# 8_steps_sequencer.net
KiCad netlist of a schematic drawn in EAGLE
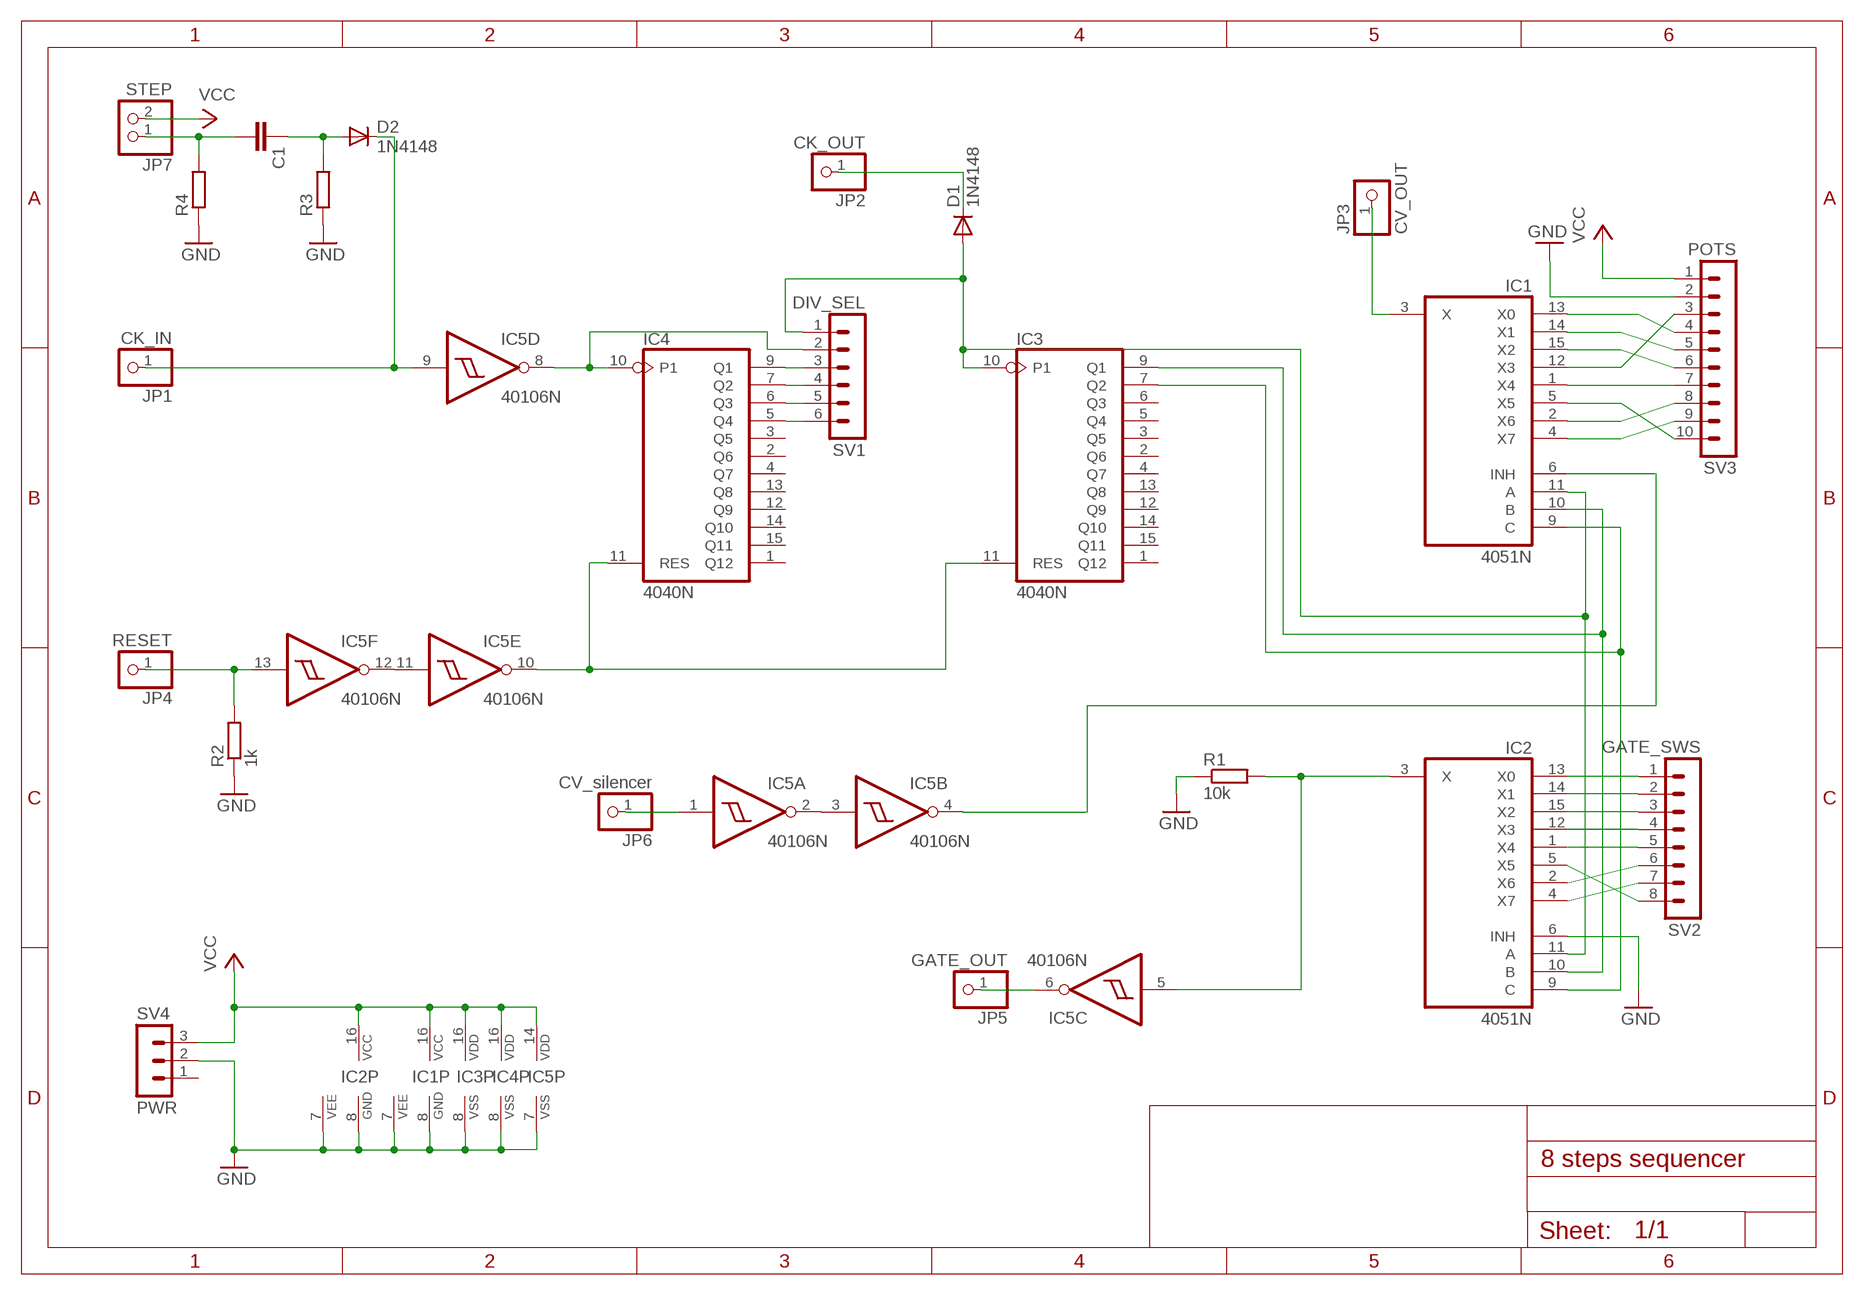
[diagram p0: schematic, sheet 1]

(export (version "E")
  (design (tool "Eeschema 10.0.6"))
  (components
    (comp (ref "C1")
      (value "C-EU025-030X050")
      (footprint "eagle-import:C025-030X050")
      (libsource (lib "eagle-import") (part "C-EU025-030X050"))
    )
    (comp (ref "D1")
      (value "1N4148")
      (footprint "eagle-import:D-2.5")
      (libsource (lib "eagle-import") (part "DIODE-D-2.5"))
    )
    (comp (ref "D2")
      (value "1N4148")
      (footprint "eagle-import:D-2.5")
      (libsource (lib "eagle-import") (part "DIODE-D-2.5"))
    )
    (comp (ref "IC1")
      (value "4051N")
      (footprint "eagle-import:DIL16")
      (libsource (lib "eagle-import") (part "4051N"))
    )
    (comp (ref "IC2")
      (value "4051N")
      (footprint "eagle-import:DIL16")
      (libsource (lib "eagle-import") (part "4051N"))
    )
    (comp (ref "IC3")
      (value "4040N")
      (footprint "eagle-import:DIL16")
      (libsource (lib "eagle-import") (part "4040N"))
    )
    (comp (ref "IC4")
      (value "4040N")
      (footprint "eagle-import:DIL16")
      (libsource (lib "eagle-import") (part "4040N"))
    )
    (comp (ref "IC5")
      (value "40106N")
      (footprint "eagle-import:DIL14")
      (libsource (lib "eagle-import") (part "40106N"))
    )
    (comp (ref "JP1")
      (value "CK_IN")
      (footprint "eagle-import:1X01")
      (libsource (lib "eagle-import") (part "PINHD-1X1"))
    )
    (comp (ref "JP2")
      (value "CK_OUT")
      (footprint "eagle-import:1X01")
      (libsource (lib "eagle-import") (part "PINHD-1X1"))
    )
    (comp (ref "JP3")
      (value "CV_OUT")
      (footprint "eagle-import:1X01")
      (libsource (lib "eagle-import") (part "PINHD-1X1"))
    )
    (comp (ref "JP4")
      (value "RESET")
      (footprint "eagle-import:1X01")
      (libsource (lib "eagle-import") (part "PINHD-1X1"))
    )
    (comp (ref "JP5")
      (value "GATE_OUT")
      (footprint "eagle-import:1X01")
      (libsource (lib "eagle-import") (part "PINHD-1X1"))
    )
    (comp (ref "JP6")
      (value "CV_silencer")
      (footprint "eagle-import:1X01")
      (libsource (lib "eagle-import") (part "PINHD-1X1"))
    )
    (comp (ref "JP7")
      (value "STEP")
      (footprint "eagle-import:1X02")
      (libsource (lib "eagle-import") (part "PINHD-1X2"))
    )
    (comp (ref "R1")
      (value "10k")
      (footprint "eagle-import:0204V")
      (libsource (lib "eagle-import") (part "R-EU_0204/2V"))
    )
    (comp (ref "R2")
      (value "1k")
      (footprint "eagle-import:0204V")
      (libsource (lib "eagle-import") (part "R-EU_0204/2V"))
    )
    (comp (ref "R3")
      (value "R-EU_0204/2V")
      (footprint "eagle-import:0204V")
      (libsource (lib "eagle-import") (part "R-EU_0204/2V"))
    )
    (comp (ref "R4")
      (value "R-EU_0204/2V")
      (footprint "eagle-import:0204V")
      (libsource (lib "eagle-import") (part "R-EU_0204/2V"))
    )
    (comp (ref "SV1")
      (value "DIV_SEL")
      (footprint "eagle-import:MA06-1")
      (libsource (lib "eagle-import") (part "MA06-1"))
    )
    (comp (ref "SV2")
      (value "GATE_SWS")
      (footprint "eagle-import:MA08-1")
      (libsource (lib "eagle-import") (part "MA08-1"))
    )
    (comp (ref "SV3")
      (value "POTS")
      (footprint "eagle-import:MA10-1")
      (libsource (lib "eagle-import") (part "MA10-1"))
    )
    (comp (ref "SV4")
      (value "PWR")
      (footprint "eagle-import:MA03-1")
      (libsource (lib "eagle-import") (part "MA03-1"))
    )
  )
  (nets
    (net (code "1") (name "GND") (class "Default")
      (node (ref "IC1") (pin "7") (pinfunction "VEE_7") (pintype "power_in"))
      (node (ref "IC1") (pin "8") (pinfunction "GND_8") (pintype "power_in"))
      (node (ref "IC2") (pin "6") (pinfunction "INH_6") (pintype "input"))
      (node (ref "IC2") (pin "7") (pinfunction "VEE_7") (pintype "power_in"))
      (node (ref "IC2") (pin "8") (pinfunction "GND_8") (pintype "power_in"))
      (node (ref "IC3") (pin "8") (pinfunction "VSS_8") (pintype "power_in"))
      (node (ref "IC4") (pin "8") (pinfunction "VSS_8") (pintype "power_in"))
      (node (ref "IC5") (pin "7") (pinfunction "VSS_7") (pintype "power_in"))
      (node (ref "R1") (pin "1") (pinfunction "1_1") (pintype "passive"))
      (node (ref "R2") (pin "1") (pinfunction "1_1") (pintype "passive"))
      (node (ref "R3") (pin "1") (pinfunction "1_1") (pintype "passive"))
      (node (ref "R4") (pin "1") (pinfunction "1_1") (pintype "passive"))
      (node (ref "SV3") (pin "2") (pinfunction "2_2") (pintype "passive"))
      (node (ref "SV4") (pin "2") (pinfunction "2_2") (pintype "passive"))
    )
    (net (code "2") (name "Net-(C1-Pad1)") (class "Default")
      (node (ref "C1") (pin "1") (pinfunction "1_1") (pintype "passive"))
      (node (ref "D2") (pin "A") (pinfunction "A_A") (pintype "passive"))
      (node (ref "R3") (pin "2") (pinfunction "2_2") (pintype "passive"))
    )
    (net (code "3") (name "Net-(C1-Pad2)") (class "Default")
      (node (ref "C1") (pin "2") (pinfunction "2_2") (pintype "passive"))
      (node (ref "JP7") (pin "1") (pinfunction "1_1") (pintype "passive"))
      (node (ref "R4") (pin "2") (pinfunction "2_2") (pintype "passive"))
    )
    (net (code "4") (name "Net-(D1-PadC)") (class "Default")
      (node (ref "D1") (pin "C") (pinfunction "C_C") (pintype "passive"))
      (node (ref "JP2") (pin "1") (pinfunction "1_1") (pintype "passive"))
    )
    (net (code "5") (name "Net-(IC1A-A)") (class "Default")
      (node (ref "D1") (pin "A") (pinfunction "A_A") (pintype "passive"))
      (node (ref "IC1") (pin "11") (pinfunction "A_11") (pintype "input"))
      (node (ref "IC2") (pin "11") (pinfunction "A_11") (pintype "input"))
      (node (ref "IC3") (pin "10") (pinfunction "P1_10") (pintype "input"))
      (node (ref "SV1") (pin "1") (pinfunction "1_1") (pintype "passive"))
    )
    (net (code "6") (name "Net-(IC1A-B)") (class "Default")
      (node (ref "IC1") (pin "10") (pinfunction "B_10") (pintype "input"))
      (node (ref "IC2") (pin "10") (pinfunction "B_10") (pintype "input"))
      (node (ref "IC3") (pin "9") (pinfunction "Q1_9") (pintype "output"))
    )
    (net (code "7") (name "Net-(IC1A-C)") (class "Default")
      (node (ref "IC1") (pin "9") (pinfunction "C_9") (pintype "input"))
      (node (ref "IC2") (pin "9") (pinfunction "C_9") (pintype "input"))
      (node (ref "IC3") (pin "7") (pinfunction "Q2_7") (pintype "output"))
    )
    (net (code "8") (name "Net-(IC1A-INH)") (class "Default")
      (node (ref "IC1") (pin "6") (pinfunction "INH_6") (pintype "input"))
      (node (ref "IC5") (pin "4") (pinfunction "O_4") (pintype "output"))
    )
    (net (code "9") (name "Net-(IC1A-X)") (class "Default")
      (node (ref "IC1") (pin "3") (pinfunction "X_3") (pintype "bidirectional"))
      (node (ref "JP3") (pin "1") (pinfunction "1_1") (pintype "passive"))
    )
    (net (code "10") (name "Net-(IC1A-X0)") (class "Default")
      (node (ref "IC1") (pin "13") (pinfunction "X0_13") (pintype "bidirectional"))
      (node (ref "SV3") (pin "4") (pinfunction "4_4") (pintype "passive"))
    )
    (net (code "11") (name "Net-(IC1A-X1)") (class "Default")
      (node (ref "IC1") (pin "14") (pinfunction "X1_14") (pintype "bidirectional"))
      (node (ref "SV3") (pin "5") (pinfunction "5_5") (pintype "passive"))
    )
    (net (code "12") (name "Net-(IC1A-X2)") (class "Default")
      (node (ref "IC1") (pin "15") (pinfunction "X2_15") (pintype "bidirectional"))
      (node (ref "SV3") (pin "6") (pinfunction "6_6") (pintype "passive"))
    )
    (net (code "13") (name "Net-(IC1A-X3)") (class "Default")
      (node (ref "IC1") (pin "12") (pinfunction "X3_12") (pintype "bidirectional"))
      (node (ref "SV3") (pin "3") (pinfunction "3_3") (pintype "passive"))
    )
    (net (code "14") (name "Net-(IC1A-X4)") (class "Default")
      (node (ref "IC1") (pin "1") (pinfunction "X4_1") (pintype "bidirectional"))
      (node (ref "SV3") (pin "7") (pinfunction "7_7") (pintype "passive"))
    )
    (net (code "15") (name "Net-(IC1A-X5)") (class "Default")
      (node (ref "IC1") (pin "5") (pinfunction "X5_5") (pintype "bidirectional"))
      (node (ref "SV3") (pin "10") (pinfunction "10_10") (pintype "passive"))
    )
    (net (code "16") (name "Net-(IC1A-X6)") (class "Default")
      (node (ref "IC1") (pin "2") (pinfunction "X6_2") (pintype "bidirectional"))
      (node (ref "SV3") (pin "8") (pinfunction "8_8") (pintype "passive"))
    )
    (net (code "17") (name "Net-(IC1A-X7)") (class "Default")
      (node (ref "IC1") (pin "4") (pinfunction "X7_4") (pintype "bidirectional"))
      (node (ref "SV3") (pin "9") (pinfunction "9_9") (pintype "passive"))
    )
    (net (code "18") (name "Net-(IC2A-X)") (class "Default")
      (node (ref "IC2") (pin "3") (pinfunction "X_3") (pintype "bidirectional"))
      (node (ref "IC5") (pin "5") (pinfunction "I_5") (pintype "input"))
      (node (ref "R1") (pin "2") (pinfunction "2_2") (pintype "passive"))
    )
    (net (code "19") (name "Net-(IC2A-X0)") (class "Default")
      (node (ref "IC2") (pin "13") (pinfunction "X0_13") (pintype "bidirectional"))
      (node (ref "SV2") (pin "1") (pinfunction "1_1") (pintype "passive"))
    )
    (net (code "20") (name "Net-(IC2A-X1)") (class "Default")
      (node (ref "IC2") (pin "14") (pinfunction "X1_14") (pintype "bidirectional"))
      (node (ref "SV2") (pin "2") (pinfunction "2_2") (pintype "passive"))
    )
    (net (code "21") (name "Net-(IC2A-X2)") (class "Default")
      (node (ref "IC2") (pin "15") (pinfunction "X2_15") (pintype "bidirectional"))
      (node (ref "SV2") (pin "3") (pinfunction "3_3") (pintype "passive"))
    )
    (net (code "22") (name "Net-(IC2A-X3)") (class "Default")
      (node (ref "IC2") (pin "12") (pinfunction "X3_12") (pintype "bidirectional"))
      (node (ref "SV2") (pin "4") (pinfunction "4_4") (pintype "passive"))
    )
    (net (code "23") (name "Net-(IC2A-X4)") (class "Default")
      (node (ref "IC2") (pin "1") (pinfunction "X4_1") (pintype "bidirectional"))
      (node (ref "SV2") (pin "5") (pinfunction "5_5") (pintype "passive"))
    )
    (net (code "24") (name "Net-(IC2A-X5)") (class "Default")
      (node (ref "IC2") (pin "5") (pinfunction "X5_5") (pintype "bidirectional"))
      (node (ref "SV2") (pin "8") (pinfunction "8_8") (pintype "passive"))
    )
    (net (code "25") (name "Net-(IC2A-X6)") (class "Default")
      (node (ref "IC2") (pin "2") (pinfunction "X6_2") (pintype "bidirectional"))
      (node (ref "SV2") (pin "6") (pinfunction "6_6") (pintype "passive"))
    )
    (net (code "26") (name "Net-(IC2A-X7)") (class "Default")
      (node (ref "IC2") (pin "4") (pinfunction "X7_4") (pintype "bidirectional"))
      (node (ref "SV2") (pin "7") (pinfunction "7_7") (pintype "passive"))
    )
    (net (code "27") (name "Net-(IC3A-RES)") (class "Default")
      (node (ref "IC3") (pin "11") (pinfunction "RES_11") (pintype "input"))
      (node (ref "IC4") (pin "11") (pinfunction "RES_11") (pintype "input"))
      (node (ref "IC5") (pin "10") (pinfunction "O_10") (pintype "output"))
    )
    (net (code "28") (name "Net-(IC4A-P1)") (class "Default")
      (node (ref "IC4") (pin "10") (pinfunction "P1_10") (pintype "input"))
      (node (ref "IC5") (pin "8") (pinfunction "O_8") (pintype "output"))
      (node (ref "SV1") (pin "2") (pinfunction "2_2") (pintype "passive"))
    )
    (net (code "29") (name "Net-(IC4A-Q1)") (class "Default")
      (node (ref "IC4") (pin "9") (pinfunction "Q1_9") (pintype "output"))
      (node (ref "SV1") (pin "3") (pinfunction "3_3") (pintype "passive"))
    )
    (net (code "30") (name "Net-(IC4A-Q2)") (class "Default")
      (node (ref "IC4") (pin "7") (pinfunction "Q2_7") (pintype "output"))
      (node (ref "SV1") (pin "4") (pinfunction "4_4") (pintype "passive"))
    )
    (net (code "31") (name "Net-(IC4A-Q3)") (class "Default")
      (node (ref "IC4") (pin "6") (pinfunction "Q3_6") (pintype "output"))
      (node (ref "SV1") (pin "5") (pinfunction "5_5") (pintype "passive"))
    )
    (net (code "32") (name "Net-(IC4A-Q4)") (class "Default")
      (node (ref "IC4") (pin "5") (pinfunction "Q4_5") (pintype "output"))
      (node (ref "SV1") (pin "6") (pinfunction "6_6") (pintype "passive"))
    )
    (net (code "33") (name "Net-(IC5A-I)") (class "Default")
      (node (ref "IC5") (pin "1") (pinfunction "I_1") (pintype "input"))
      (node (ref "JP6") (pin "1") (pinfunction "1_1") (pintype "passive"))
    )
    (net (code "34") (name "Net-(IC5A-O)") (class "Default")
      (node (ref "IC5") (pin "2") (pinfunction "O_2") (pintype "output"))
      (node (ref "IC5") (pin "3") (pinfunction "I_3") (pintype "input"))
    )
    (net (code "35") (name "Net-(IC5C-O)") (class "Default")
      (node (ref "IC5") (pin "6") (pinfunction "O_6") (pintype "output"))
      (node (ref "JP5") (pin "1") (pinfunction "1_1") (pintype "passive"))
    )
    (net (code "36") (name "Net-(IC5D-I)") (class "Default")
      (node (ref "D2") (pin "C") (pinfunction "C_C") (pintype "passive"))
      (node (ref "IC5") (pin "9") (pinfunction "I_9") (pintype "input"))
      (node (ref "JP1") (pin "1") (pinfunction "1_1") (pintype "passive"))
    )
    (net (code "37") (name "Net-(IC5E-I)") (class "Default")
      (node (ref "IC5") (pin "11") (pinfunction "I_11") (pintype "input"))
      (node (ref "IC5") (pin "12") (pinfunction "O_12") (pintype "output"))
    )
    (net (code "38") (name "Net-(IC5F-I)") (class "Default")
      (node (ref "IC5") (pin "13") (pinfunction "I_13") (pintype "input"))
      (node (ref "JP4") (pin "1") (pinfunction "1_1") (pintype "passive"))
      (node (ref "R2") (pin "2") (pinfunction "2_2") (pintype "passive"))
    )
    (net (code "39") (name "VCC") (class "Default")
      (node (ref "IC1") (pin "16") (pinfunction "VCC_16") (pintype "power_in"))
      (node (ref "IC2") (pin "16") (pinfunction "VCC_16") (pintype "power_in"))
      (node (ref "IC3") (pin "16") (pinfunction "VDD_16") (pintype "power_in"))
      (node (ref "IC4") (pin "16") (pinfunction "VDD_16") (pintype "power_in"))
      (node (ref "IC5") (pin "14") (pinfunction "VDD_14") (pintype "power_in"))
      (node (ref "JP7") (pin "2") (pinfunction "2_2") (pintype "passive"))
      (node (ref "SV3") (pin "1") (pinfunction "1_1") (pintype "passive"))
      (node (ref "SV4") (pin "3") (pinfunction "3_3") (pintype "passive"))
    )
    (net (code "40") (name "unconnected-(IC3A-Q3-Pad6)") (class "Default")
      (node (ref "IC3") (pin "6") (pinfunction "Q3_6") (pintype "output"))
    )
    (net (code "41") (name "unconnected-(IC3A-Q4-Pad5)") (class "Default")
      (node (ref "IC3") (pin "5") (pinfunction "Q4_5") (pintype "output"))
    )
    (net (code "42") (name "unconnected-(IC3A-Q5-Pad3)") (class "Default")
      (node (ref "IC3") (pin "3") (pinfunction "Q5_3") (pintype "output"))
    )
    (net (code "43") (name "unconnected-(IC3A-Q6-Pad2)") (class "Default")
      (node (ref "IC3") (pin "2") (pinfunction "Q6_2") (pintype "output"))
    )
    (net (code "44") (name "unconnected-(IC3A-Q7-Pad4)") (class "Default")
      (node (ref "IC3") (pin "4") (pinfunction "Q7_4") (pintype "output"))
    )
    (net (code "45") (name "unconnected-(IC3A-Q8-Pad13)") (class "Default")
      (node (ref "IC3") (pin "13") (pinfunction "Q8_13") (pintype "output"))
    )
    (net (code "46") (name "unconnected-(IC3A-Q9-Pad12)") (class "Default")
      (node (ref "IC3") (pin "12") (pinfunction "Q9_12") (pintype "output"))
    )
    (net (code "47") (name "unconnected-(IC3A-Q10-Pad14)") (class "Default")
      (node (ref "IC3") (pin "14") (pinfunction "Q10_14") (pintype "output"))
    )
    (net (code "48") (name "unconnected-(IC3A-Q11-Pad15)") (class "Default")
      (node (ref "IC3") (pin "15") (pinfunction "Q11_15") (pintype "output"))
    )
    (net (code "49") (name "unconnected-(IC3A-Q12-Pad1)") (class "Default")
      (node (ref "IC3") (pin "1") (pinfunction "Q12_1") (pintype "output"))
    )
    (net (code "50") (name "unconnected-(IC4A-Q5-Pad3)") (class "Default")
      (node (ref "IC4") (pin "3") (pinfunction "Q5_3") (pintype "output"))
    )
    (net (code "51") (name "unconnected-(IC4A-Q6-Pad2)") (class "Default")
      (node (ref "IC4") (pin "2") (pinfunction "Q6_2") (pintype "output"))
    )
    (net (code "52") (name "unconnected-(IC4A-Q7-Pad4)") (class "Default")
      (node (ref "IC4") (pin "4") (pinfunction "Q7_4") (pintype "output"))
    )
    (net (code "53") (name "unconnected-(IC4A-Q8-Pad13)") (class "Default")
      (node (ref "IC4") (pin "13") (pinfunction "Q8_13") (pintype "output"))
    )
    (net (code "54") (name "unconnected-(IC4A-Q9-Pad12)") (class "Default")
      (node (ref "IC4") (pin "12") (pinfunction "Q9_12") (pintype "output"))
    )
    (net (code "55") (name "unconnected-(IC4A-Q10-Pad14)") (class "Default")
      (node (ref "IC4") (pin "14") (pinfunction "Q10_14") (pintype "output"))
    )
    (net (code "56") (name "unconnected-(IC4A-Q11-Pad15)") (class "Default")
      (node (ref "IC4") (pin "15") (pinfunction "Q11_15") (pintype "output"))
    )
    (net (code "57") (name "unconnected-(IC4A-Q12-Pad1)") (class "Default")
      (node (ref "IC4") (pin "1") (pinfunction "Q12_1") (pintype "output"))
    )
    (net (code "58") (name "unconnected-(SV4-Pad1)") (class "Default")
      (node (ref "SV4") (pin "1") (pinfunction "1_1") (pintype "passive"))
    )
  )
)
